# SmartCar_Arduino_V2.net
KiCad netlist of a schematic drawn in EAGLE
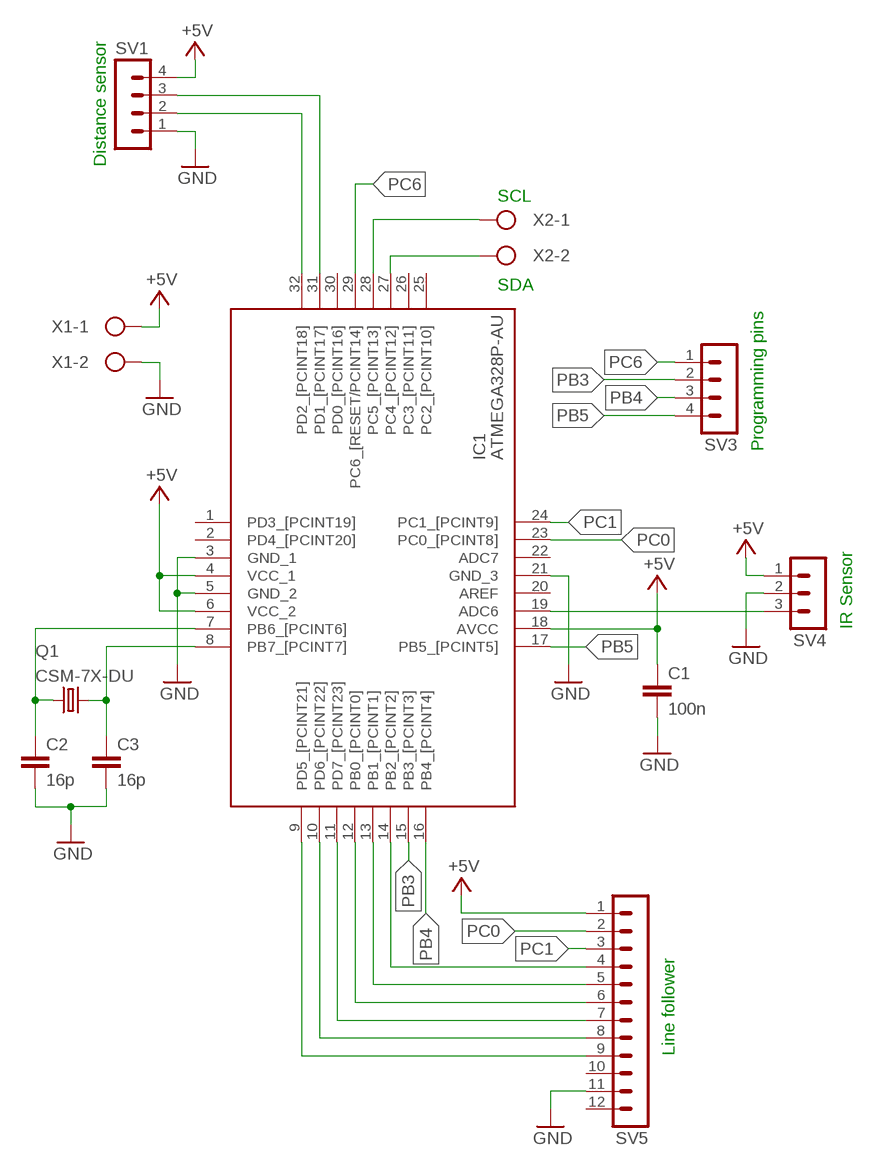
[diagram p0: schematic, sheet 1]

(export (version "E")
  (design (tool "Eeschema 10.0.6"))
  (components
    (comp (ref "C1")
      (value "100n")
      (footprint "eagle-import:C0805")
      (libsource (lib "eagle-import") (part "C-EUC0805"))
    )
    (comp (ref "C2")
      (value "16p")
      (footprint "eagle-import:C0805")
      (libsource (lib "eagle-import") (part "C-EUC0805"))
    )
    (comp (ref "C3")
      (value "16p")
      (footprint "eagle-import:C0805")
      (libsource (lib "eagle-import") (part "C-EUC0805"))
    )
    (comp (ref "IC1")
      (value "ATMEGA328P-AU")
      (footprint "eagle-import:QFP80P900X900X120-32N")
      (fields (field (name "MOUSER_PART_NUMBER") "556-ATMEGA328P-AU"))
      (libsource (lib "eagle-import") (part "ATMEGA328P-AU"))
    )
    (comp (ref "Q1")
      (value "CSM-7X-DU")
      (footprint "eagle-import:CSM-7X-DU")
      (libsource (lib "eagle-import") (part "CSM-7X-DU"))
    )
    (comp (ref "SV1")
      (value "MA04-1")
      (footprint "eagle-import:MA04-1")
      (libsource (lib "eagle-import") (part "MA04-1"))
    )
    (comp (ref "SV3")
      (value "MA04-1")
      (footprint "eagle-import:MA04-1")
      (libsource (lib "eagle-import") (part "MA04-1"))
    )
    (comp (ref "SV4")
      (value "MA03-1")
      (footprint "eagle-import:MA03-1")
      (libsource (lib "eagle-import") (part "MA03-1"))
    )
    (comp (ref "SV5")
      (value "MA12-1")
      (footprint "eagle-import:MA12-1")
      (libsource (lib "eagle-import") (part "MA12-1"))
    )
    (comp (ref "X1")
      (value "W237-102")
      (footprint "eagle-import:W237-102")
      (fields (field (name "MPN") "237-102"))
      (libsource (lib "eagle-import") (part "W237-102"))
    )
    (comp (ref "X2")
      (value "W237-102")
      (footprint "eagle-import:W237-102")
      (fields (field (name "MPN") "237-102"))
      (libsource (lib "eagle-import") (part "W237-102"))
    )
  )
  (nets
    (net (code "1") (name "+5V") (class "Default")
      (node (ref "C1") (pin "1") (pinfunction "1_1") (pintype "passive"))
      (node (ref "IC1") (pin "18") (pinfunction "AVCC_18") (pintype "power_in"))
      (node (ref "IC1") (pin "4") (pinfunction "VCC_1_4") (pintype "power_in"))
      (node (ref "IC1") (pin "6") (pinfunction "VCC_2_6") (pintype "power_in"))
      (node (ref "SV1") (pin "4") (pinfunction "4_4") (pintype "passive"))
      (node (ref "SV4") (pin "1") (pinfunction "1_1") (pintype "passive"))
      (node (ref "SV5") (pin "1") (pinfunction "1_1") (pintype "passive"))
      (node (ref "X1") (pin "1") (pinfunction "KL_1") (pintype "passive"))
    )
    (net (code "2") (name "GND") (class "Default")
      (node (ref "C1") (pin "2") (pinfunction "2_2") (pintype "passive"))
      (node (ref "C2") (pin "2") (pinfunction "2_2") (pintype "passive"))
      (node (ref "C3") (pin "2") (pinfunction "2_2") (pintype "passive"))
      (node (ref "IC1") (pin "21") (pinfunction "GND_3_21") (pintype "power_in"))
      (node (ref "IC1") (pin "3") (pinfunction "GND_1_3") (pintype "power_in"))
      (node (ref "IC1") (pin "5") (pinfunction "GND_2_5") (pintype "power_in"))
      (node (ref "SV1") (pin "1") (pinfunction "1_1") (pintype "passive"))
      (node (ref "SV4") (pin "2") (pinfunction "2_2") (pintype "passive"))
      (node (ref "SV5") (pin "11") (pinfunction "11_11") (pintype "passive"))
      (node (ref "X1") (pin "2") (pinfunction "KL_2") (pintype "passive"))
    )
    (net (code "3") (name "Net-(IC1-ADC6)") (class "Default")
      (node (ref "IC1") (pin "19") (pinfunction "ADC6_19") (pintype "bidirectional"))
      (node (ref "SV4") (pin "3") (pinfunction "3_3") (pintype "passive"))
    )
    (net (code "4") (name "Net-(IC1-PB0_[PCINT0])") (class "Default")
      (node (ref "IC1") (pin "12") (pinfunction "PB0_[PCINT0]_12") (pintype "bidirectional"))
      (node (ref "SV5") (pin "6") (pinfunction "6_6") (pintype "passive"))
    )
    (net (code "5") (name "Net-(IC1-PB1_[PCINT1])") (class "Default")
      (node (ref "IC1") (pin "13") (pinfunction "PB1_[PCINT1]_13") (pintype "bidirectional"))
      (node (ref "SV5") (pin "5") (pinfunction "5_5") (pintype "passive"))
    )
    (net (code "6") (name "Net-(IC1-PB2_[PCINT2])") (class "Default")
      (node (ref "IC1") (pin "14") (pinfunction "PB2_[PCINT2]_14") (pintype "bidirectional"))
      (node (ref "SV5") (pin "4") (pinfunction "4_4") (pintype "passive"))
    )
    (net (code "7") (name "Net-(IC1-PB6_[PCINT6])") (class "Default")
      (node (ref "C2") (pin "1") (pinfunction "1_1") (pintype "passive"))
      (node (ref "IC1") (pin "7") (pinfunction "PB6_[PCINT6]_7") (pintype "bidirectional"))
      (node (ref "Q1") (pin "1") (pinfunction "1_1") (pintype "passive"))
    )
    (net (code "8") (name "Net-(IC1-PB7_[PCINT7])") (class "Default")
      (node (ref "C3") (pin "1") (pinfunction "1_1") (pintype "passive"))
      (node (ref "IC1") (pin "8") (pinfunction "PB7_[PCINT7]_8") (pintype "bidirectional"))
      (node (ref "Q1") (pin "2") (pinfunction "2_2") (pintype "passive"))
    )
    (net (code "9") (name "Net-(IC1-PC4_[PCINT12])") (class "Default")
      (node (ref "IC1") (pin "27") (pinfunction "PC4_[PCINT12]_27") (pintype "bidirectional"))
      (node (ref "X2") (pin "2") (pinfunction "KL_2") (pintype "passive"))
    )
    (net (code "10") (name "Net-(IC1-PC5_[PCINT13])") (class "Default")
      (node (ref "IC1") (pin "28") (pinfunction "PC5_[PCINT13]_28") (pintype "bidirectional"))
      (node (ref "X2") (pin "1") (pinfunction "KL_1") (pintype "passive"))
    )
    (net (code "11") (name "Net-(IC1-PD1_[PCINT17])") (class "Default")
      (node (ref "IC1") (pin "31") (pinfunction "PD1_[PCINT17]_31") (pintype "bidirectional"))
      (node (ref "SV1") (pin "3") (pinfunction "3_3") (pintype "passive"))
    )
    (net (code "12") (name "Net-(IC1-PD2_[PCINT18])") (class "Default")
      (node (ref "IC1") (pin "32") (pinfunction "PD2_[PCINT18]_32") (pintype "bidirectional"))
      (node (ref "SV1") (pin "2") (pinfunction "2_2") (pintype "passive"))
    )
    (net (code "13") (name "Net-(IC1-PD5_[PCINT21])") (class "Default")
      (node (ref "IC1") (pin "9") (pinfunction "PD5_[PCINT21]_9") (pintype "bidirectional"))
      (node (ref "SV5") (pin "9") (pinfunction "9_9") (pintype "passive"))
    )
    (net (code "14") (name "Net-(IC1-PD6_[PCINT22])") (class "Default")
      (node (ref "IC1") (pin "10") (pinfunction "PD6_[PCINT22]_10") (pintype "bidirectional"))
      (node (ref "SV5") (pin "8") (pinfunction "8_8") (pintype "passive"))
    )
    (net (code "15") (name "Net-(IC1-PD7_[PCINT23])") (class "Default")
      (node (ref "IC1") (pin "11") (pinfunction "PD7_[PCINT23]_11") (pintype "bidirectional"))
      (node (ref "SV5") (pin "7") (pinfunction "7_7") (pintype "passive"))
    )
    (net (code "16") (name "PB3") (class "Default")
      (node (ref "IC1") (pin "15") (pinfunction "PB3_[PCINT3]_15") (pintype "bidirectional"))
      (node (ref "SV3") (pin "2") (pinfunction "2_2") (pintype "passive"))
    )
    (net (code "17") (name "PB4") (class "Default")
      (node (ref "IC1") (pin "16") (pinfunction "PB4_[PCINT4]_16") (pintype "bidirectional"))
      (node (ref "SV3") (pin "3") (pinfunction "3_3") (pintype "passive"))
    )
    (net (code "18") (name "PB5") (class "Default")
      (node (ref "IC1") (pin "17") (pinfunction "PB5_[PCINT5]_17") (pintype "bidirectional"))
      (node (ref "SV3") (pin "4") (pinfunction "4_4") (pintype "passive"))
    )
    (net (code "19") (name "PC0") (class "Default")
      (node (ref "IC1") (pin "23") (pinfunction "PC0_[PCINT8]_23") (pintype "bidirectional"))
      (node (ref "SV5") (pin "2") (pinfunction "2_2") (pintype "passive"))
    )
    (net (code "20") (name "PC1") (class "Default")
      (node (ref "IC1") (pin "24") (pinfunction "PC1_[PCINT9]_24") (pintype "bidirectional"))
      (node (ref "SV5") (pin "3") (pinfunction "3_3") (pintype "passive"))
    )
    (net (code "21") (name "PC6") (class "Default")
      (node (ref "IC1") (pin "29") (pinfunction "PC6_[RESET/PCINT14]_29") (pintype "bidirectional"))
      (node (ref "SV3") (pin "1") (pinfunction "1_1") (pintype "passive"))
    )
    (net (code "22") (name "unconnected-(IC1-ADC7-Pad22)") (class "Default")
      (node (ref "IC1") (pin "22") (pinfunction "ADC7_22") (pintype "bidirectional"))
    )
    (net (code "23") (name "unconnected-(IC1-AREF-Pad20)") (class "Default")
      (node (ref "IC1") (pin "20") (pinfunction "AREF_20") (pintype "bidirectional"))
    )
    (net (code "24") (name "unconnected-(IC1-PC2_[PCINT10]-Pad25)") (class "Default")
      (node (ref "IC1") (pin "25") (pinfunction "PC2_[PCINT10]_25") (pintype "bidirectional"))
    )
    (net (code "25") (name "unconnected-(IC1-PC3_[PCINT11]-Pad26)") (class "Default")
      (node (ref "IC1") (pin "26") (pinfunction "PC3_[PCINT11]_26") (pintype "bidirectional"))
    )
    (net (code "26") (name "unconnected-(IC1-PD0_[PCINT16]-Pad30)") (class "Default")
      (node (ref "IC1") (pin "30") (pinfunction "PD0_[PCINT16]_30") (pintype "bidirectional"))
    )
    (net (code "27") (name "unconnected-(IC1-PD3_[PCINT19]-Pad1)") (class "Default")
      (node (ref "IC1") (pin "1") (pinfunction "PD3_[PCINT19]_1") (pintype "bidirectional"))
    )
    (net (code "28") (name "unconnected-(IC1-PD4_[PCINT20]-Pad2)") (class "Default")
      (node (ref "IC1") (pin "2") (pinfunction "PD4_[PCINT20]_2") (pintype "bidirectional"))
    )
    (net (code "29") (name "unconnected-(SV5-Pad10)") (class "Default")
      (node (ref "SV5") (pin "10") (pinfunction "10_10") (pintype "passive"))
    )
    (net (code "30") (name "unconnected-(SV5-Pad12)") (class "Default")
      (node (ref "SV5") (pin "12") (pinfunction "12_12") (pintype "passive"))
    )
  )
)
